# iSENSE_Data_Logger.net
KiCad netlist of a schematic drawn in EAGLE
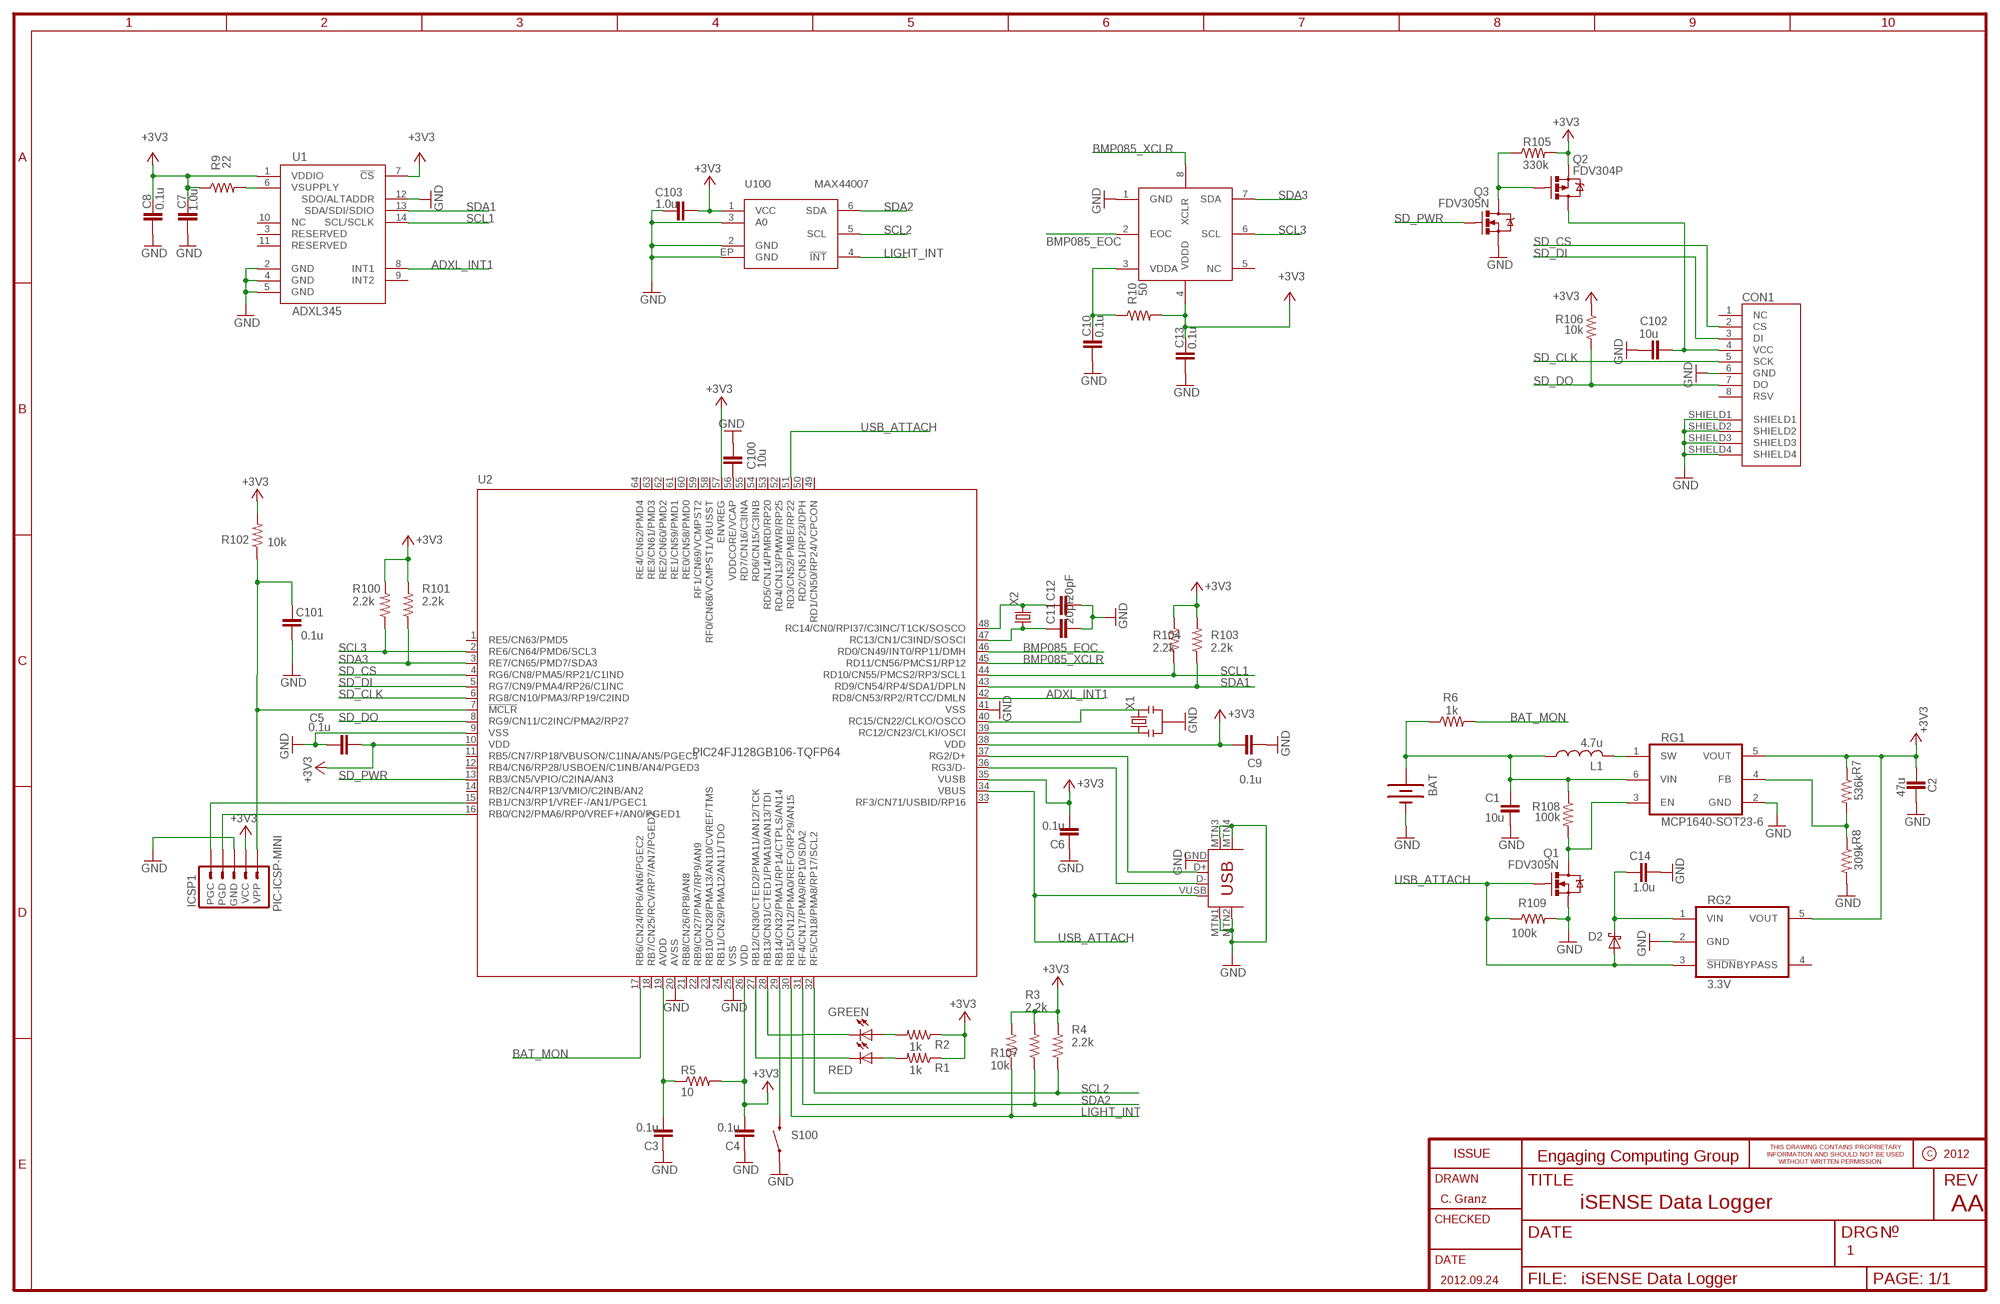
[diagram p0: schematic, sheet 1]

(export (version "E")
  (design (tool "Eeschema 10.0.6"))
  (components
    (comp (ref "BAT")
      (value "BATTERY-AAA-PCB-1-NO-HOLES")
      (footprint "eagle-import:BATTERY_HOLDER_AAA_KEYSTONE_2466_NO_HOLES")
      (libsource (lib "eagle-import") (part "BATTERY-AAA-PCB-1-NO-HOLES"))
    )
    (comp (ref "C1")
      (value "10u")
      (footprint "eagle-import:RCL_0603")
      (libsource (lib "eagle-import") (part "CAPACITOR-0603"))
    )
    (comp (ref "C2")
      (value "47u")
      (footprint "eagle-import:RCL_0603")
      (libsource (lib "eagle-import") (part "CAPACITOR-0603"))
    )
    (comp (ref "C3")
      (value "0.1u")
      (footprint "eagle-import:RCL_0402")
      (libsource (lib "eagle-import") (part "CAPACITOR-0402"))
    )
    (comp (ref "C4")
      (value "0.1u")
      (footprint "eagle-import:RCL_0402")
      (libsource (lib "eagle-import") (part "CAPACITOR-0402"))
    )
    (comp (ref "C5")
      (value "0.1u")
      (footprint "eagle-import:RCL_0402")
      (libsource (lib "eagle-import") (part "CAPACITOR-0402"))
    )
    (comp (ref "C6")
      (value "0.1u")
      (footprint "eagle-import:RCL_0402")
      (libsource (lib "eagle-import") (part "CAPACITOR-0402"))
    )
    (comp (ref "C7")
      (value "1.0u")
      (footprint "eagle-import:RCL_0402")
      (libsource (lib "eagle-import") (part "CAPACITOR-0402"))
    )
    (comp (ref "C8")
      (value "0.1u")
      (footprint "eagle-import:RCL_0402")
      (libsource (lib "eagle-import") (part "CAPACITOR-0402"))
    )
    (comp (ref "C9")
      (value "0.1u")
      (footprint "eagle-import:RCL_0402")
      (libsource (lib "eagle-import") (part "CAPACITOR-0402"))
    )
    (comp (ref "C10")
      (value "0.1u")
      (footprint "eagle-import:RCL_0402")
      (libsource (lib "eagle-import") (part "CAPACITOR-0402"))
    )
    (comp (ref "C11")
      (value "20pF")
      (footprint "eagle-import:RCL_0402")
      (libsource (lib "eagle-import") (part "CAPACITOR-0402"))
    )
    (comp (ref "C12")
      (value "20pF")
      (footprint "eagle-import:RCL_0402")
      (libsource (lib "eagle-import") (part "CAPACITOR-0402"))
    )
    (comp (ref "C13")
      (value "0.1u")
      (footprint "eagle-import:RCL_0402")
      (libsource (lib "eagle-import") (part "CAPACITOR-0402"))
    )
    (comp (ref "C14")
      (value "1.0u")
      (footprint "eagle-import:RCL_0603")
      (libsource (lib "eagle-import") (part "CAPACITOR-0603"))
    )
    (comp (ref "C100")
      (value "10u")
      (footprint "eagle-import:RCL_0603")
      (libsource (lib "eagle-import") (part "CAPACITOR-0603"))
    )
    (comp (ref "C101")
      (value "0.1u")
      (footprint "eagle-import:RCL_0402")
      (libsource (lib "eagle-import") (part "CAPACITOR-0402"))
    )
    (comp (ref "C102")
      (value "10u")
      (footprint "eagle-import:RCL_0402")
      (libsource (lib "eagle-import") (part "CAPACITOR-0402"))
    )
    (comp (ref "C103")
      (value "1.0u")
      (footprint "eagle-import:RCL_0402")
      (libsource (lib "eagle-import") (part "CAPACITOR-0402"))
    )
    (comp (ref "CON1")
      (value "SOCKET_SD_CARD_MICRO-AMP-101-00303-68")
      (footprint "eagle-import:SOCKET_SD_CARD_MICRO")
      (fields (field (name "PN") "101-00303-68"))
      (libsource (lib "eagle-import") (part "SOCKET_SD_CARD_MICRO-AMP-101-00303-68"))
    )
    (comp (ref "D2")
      (value "DIODE_SCHOTTKY-SOD523")
      (footprint "eagle-import:SOD523")
      (libsource (lib "eagle-import") (part "DIODE_SCHOTTKY-SOD523"))
    )
    (comp (ref "GREEN")
      (value "GREEN")
      (footprint "eagle-import:LED_0603")
      (libsource (lib "eagle-import") (part "LED-0603"))
    )
    (comp (ref "ICSP1")
      (value "PIC-ICSP-MINI")
      (footprint "eagle-import:PIC-ICSP-MINI")
      (libsource (lib "eagle-import") (part "PIC-ICSP-MINI"))
    )
    (comp (ref "L1")
      (value "4.7u")
      (footprint "eagle-import:INDUCTOR_3MM_X_3MM")
      (libsource (lib "eagle-import") (part "INDUCTOR-3X3MM"))
    )
    (comp (ref "Q1")
      (value "FDV305N")
      (footprint "eagle-import:SOT23-3")
      (fields (field (name "PN") "FDV305N"))
      (libsource (lib "eagle-import") (part "FDV305N"))
    )
    (comp (ref "Q2")
      (value "FDV304P")
      (footprint "eagle-import:SOT23-3")
      (fields (field (name "PN") "FDV304P"))
      (libsource (lib "eagle-import") (part "FDV302P"))
    )
    (comp (ref "Q3")
      (value "FDV305N")
      (footprint "eagle-import:SOT23-3")
      (fields (field (name "PN") "FDV305N"))
      (libsource (lib "eagle-import") (part "FDV305N"))
    )
    (comp (ref "R1")
      (value "1k")
      (footprint "eagle-import:RCL_0402")
      (libsource (lib "eagle-import") (part "RESISTOR-0402"))
    )
    (comp (ref "R2")
      (value "1k")
      (footprint "eagle-import:RCL_0402")
      (libsource (lib "eagle-import") (part "RESISTOR-0402"))
    )
    (comp (ref "R3")
      (value "2.2k")
      (footprint "eagle-import:RCL_0402")
      (libsource (lib "eagle-import") (part "RESISTOR-0402"))
    )
    (comp (ref "R4")
      (value "2.2k")
      (footprint "eagle-import:RCL_0402")
      (libsource (lib "eagle-import") (part "RESISTOR-0402"))
    )
    (comp (ref "R5")
      (value "10")
      (footprint "eagle-import:RCL_0402")
      (libsource (lib "eagle-import") (part "RESISTOR-0402"))
    )
    (comp (ref "R6")
      (value "1k")
      (footprint "eagle-import:RCL_0402")
      (libsource (lib "eagle-import") (part "RESISTOR-0402"))
    )
    (comp (ref "R7")
      (value "536k")
      (footprint "eagle-import:RCL_0402")
      (libsource (lib "eagle-import") (part "RESISTOR-0402"))
    )
    (comp (ref "R8")
      (value "309k")
      (footprint "eagle-import:RCL_0402")
      (libsource (lib "eagle-import") (part "RESISTOR-0402"))
    )
    (comp (ref "R9")
      (value "22")
      (footprint "eagle-import:RCL_0402")
      (libsource (lib "eagle-import") (part "RESISTOR-0402"))
    )
    (comp (ref "R10")
      (value "50")
      (footprint "eagle-import:RCL_0402")
      (libsource (lib "eagle-import") (part "RESISTOR-0402"))
    )
    (comp (ref "R100")
      (value "2.2k")
      (footprint "eagle-import:RCL_0402")
      (libsource (lib "eagle-import") (part "RESISTOR-0402"))
    )
    (comp (ref "R101")
      (value "2.2k")
      (footprint "eagle-import:RCL_0402")
      (libsource (lib "eagle-import") (part "RESISTOR-0402"))
    )
    (comp (ref "R102")
      (value "10k")
      (footprint "eagle-import:RCL_0402")
      (libsource (lib "eagle-import") (part "RESISTOR-0402"))
    )
    (comp (ref "R103")
      (value "2.2k")
      (footprint "eagle-import:RCL_0402")
      (libsource (lib "eagle-import") (part "RESISTOR-0402"))
    )
    (comp (ref "R104")
      (value "2.2k")
      (footprint "eagle-import:RCL_0402")
      (libsource (lib "eagle-import") (part "RESISTOR-0402"))
    )
    (comp (ref "R105")
      (value "330k")
      (footprint "eagle-import:RCL_0402")
      (libsource (lib "eagle-import") (part "RESISTOR-0402"))
    )
    (comp (ref "R106")
      (value "10k")
      (footprint "eagle-import:RCL_0402")
      (libsource (lib "eagle-import") (part "RESISTOR-0402"))
    )
    (comp (ref "R107")
      (value "10k")
      (footprint "eagle-import:RCL_0402")
      (libsource (lib "eagle-import") (part "RESISTOR-0402"))
    )
    (comp (ref "R108")
      (value "100k")
      (footprint "eagle-import:RCL_0402")
      (libsource (lib "eagle-import") (part "RESISTOR-0402"))
    )
    (comp (ref "R109")
      (value "100k")
      (footprint "eagle-import:RCL_0402")
      (libsource (lib "eagle-import") (part "RESISTOR-0402"))
    )
    (comp (ref "RED")
      (value "RED")
      (footprint "eagle-import:LED_0603")
      (libsource (lib "eagle-import") (part "LED-0603"))
    )
    (comp (ref "RG1")
      (value "MCP1640-SOT23-6")
      (footprint "eagle-import:SOT23-6")
      (libsource (lib "eagle-import") (part "MCP1640-SOT23-6"))
    )
    (comp (ref "RG2")
      (value "3.3V")
      (footprint "eagle-import:SOT23-5")
      (libsource (lib "eagle-import") (part "TC1015"))
    )
    (comp (ref "S100")
      (value "SWITCH_MOMENTARY-SMD-RA")
      (footprint "eagle-import:SWITCH_TACTILE_SMD_RA")
      (libsource (lib "eagle-import") (part "SWITCH_MOMENTARY-SMD-RA"))
    )
    (comp (ref "U1")
      (value "ADXL345")
      (footprint "eagle-import:LGA14")
      (libsource (lib "eagle-import") (part "ADXL345"))
    )
    (comp (ref "U2")
      (value "PIC24FJ128GB106-TQFP64")
      (footprint "eagle-import:TQFP64-10X10")
      (fields (field (name "PN") "PIC24FJ128GB106-I/PT"))
      (libsource (lib "eagle-import") (part "PIC24FJ128GB106-TQFP64"))
    )
    (comp (ref "U3")
      (value "BMP085")
      (footprint "eagle-import:BMP085")
      (fields (field (name "PN") "BMP085"))
      (libsource (lib "eagle-import") (part "BMP085"))
    )
    (comp (ref "U100")
      (value "MAX44007")
      (footprint "eagle-import:UTDFN-OPTO")
      (libsource (lib "eagle-import") (part "MAX44007"))
    )
    (comp (ref "USB100")
      (value "CON_USB_4_PIN-A_MALE")
      (footprint "eagle-import:CON_USB_A_MALE_CNC_TECH_1001-010-01001")
      (fields (field (name "PN") "1001-010-01001"))
      (libsource (lib "eagle-import") (part "CON_USB_4_PIN-A_MALE"))
    )
    (comp (ref "X1")
      (value "CERAMIC_RESONATOR_3_PIN-2MM_X_4.5MM")
      (footprint "eagle-import:CERAMIC_RESONATOR_MURATA_2X4.5")
      (libsource (lib "eagle-import") (part "CERAMIC_RESONATOR_3_PIN-2MM_X_4.5MM"))
    )
    (comp (ref "X2")
      (value "CRYSTAL_2_PIN-4.9MM_X_1.8MM")
      (footprint "eagle-import:CRYSTAL_ABRACON_ABS10")
      (libsource (lib "eagle-import") (part "CRYSTAL_2_PIN-4.9MM_X_1.8MM"))
    )
  )
  (nets
    (net (code "1") (name "+3V3") (class "Default")
      (node (ref "C103") (pin "1") (pinfunction "1_1") (pintype "passive"))
      (node (ref "C13") (pin "2") (pinfunction "2_2") (pintype "passive"))
      (node (ref "C2") (pin "1") (pinfunction "1_1") (pintype "passive"))
      (node (ref "C4") (pin "2") (pinfunction "2_2") (pintype "passive"))
      (node (ref "C5") (pin "1") (pinfunction "1_1") (pintype "passive"))
      (node (ref "C6") (pin "2") (pinfunction "2_2") (pintype "passive"))
      (node (ref "C7") (pin "2") (pinfunction "2_2") (pintype "passive"))
      (node (ref "C8") (pin "2") (pinfunction "2_2") (pintype "passive"))
      (node (ref "C9") (pin "1") (pinfunction "1_1") (pintype "passive"))
      (node (ref "ICSP1") (pin "2") (pinfunction "VCC_2") (pintype "passive"))
      (node (ref "Q2") (pin "2") (pinfunction "S_2") (pintype "passive"))
      (node (ref "R1") (pin "1") (pinfunction "1_1") (pintype "passive"))
      (node (ref "R10") (pin "2") (pinfunction "2_2") (pintype "passive"))
      (node (ref "R100") (pin "2") (pinfunction "2_2") (pintype "passive"))
      (node (ref "R101") (pin "2") (pinfunction "2_2") (pintype "passive"))
      (node (ref "R102") (pin "2") (pinfunction "2_2") (pintype "passive"))
      (node (ref "R103") (pin "2") (pinfunction "2_2") (pintype "passive"))
      (node (ref "R104") (pin "2") (pinfunction "2_2") (pintype "passive"))
      (node (ref "R105") (pin "2") (pinfunction "2_2") (pintype "passive"))
      (node (ref "R106") (pin "1") (pinfunction "1_1") (pintype "passive"))
      (node (ref "R107") (pin "2") (pinfunction "2_2") (pintype "passive"))
      (node (ref "R2") (pin "1") (pinfunction "1_1") (pintype "passive"))
      (node (ref "R3") (pin "2") (pinfunction "2_2") (pintype "passive"))
      (node (ref "R4") (pin "2") (pinfunction "2_2") (pintype "passive"))
      (node (ref "R5") (pin "2") (pinfunction "2_2") (pintype "passive"))
      (node (ref "R7") (pin "1") (pinfunction "1_1") (pintype "passive"))
      (node (ref "R9") (pin "1") (pinfunction "1_1") (pintype "passive"))
      (node (ref "RG1") (pin "5") (pinfunction "VOUT_5") (pintype "power_in"))
      (node (ref "RG2") (pin "5") (pinfunction "VOUT_5") (pintype "power_in"))
      (node (ref "U1") (pin "1") (pinfunction "VDDIO_1") (pintype "power_in"))
      (node (ref "U1") (pin "7") (pinfunction "~{CS}_7") (pintype "input"))
      (node (ref "U100") (pin "1") (pinfunction "VCC_1") (pintype "bidirectional"))
      (node (ref "U2") (pin "10") (pinfunction "VDD_10") (pintype "power_in"))
      (node (ref "U2") (pin "26") (pinfunction "VDD_26") (pintype "power_in"))
      (node (ref "U2") (pin "35") (pinfunction "VUSB_35") (pintype "bidirectional"))
      (node (ref "U2") (pin "38") (pinfunction "VDD_38") (pintype "power_in"))
      (node (ref "U2") (pin "57") (pinfunction "ENVREG_57") (pintype "bidirectional"))
      (node (ref "U3") (pin "4") (pinfunction "VDDD_4") (pintype "power_in"))
    )
    (net (code "2") (name "/ADXL_INT1") (class "Default")
      (node (ref "U1") (pin "8") (pinfunction "INT1_8") (pintype "output"))
      (node (ref "U2") (pin "42") (pinfunction "RD8/CN53/RP2/RTCC/DMLN_42") (pintype "bidirectional"))
    )
    (net (code "3") (name "/BAT_MON") (class "Default")
      (node (ref "R6") (pin "2") (pinfunction "2_2") (pintype "passive"))
      (node (ref "U2") (pin "17") (pinfunction "RB6/CN24/RP6/AN6/PGEC2_17") (pintype "bidirectional"))
    )
    (net (code "4") (name "/BMP085_EOC") (class "Default")
      (node (ref "U2") (pin "46") (pinfunction "RD0/CN49/INT0/RP11/DMH_46") (pintype "bidirectional"))
      (node (ref "U3") (pin "2") (pinfunction "EOC_2") (pintype "bidirectional"))
    )
    (net (code "5") (name "/BMP085_XCLR") (class "Default")
      (node (ref "U2") (pin "45") (pinfunction "RD11/CN56/PMCS1/RP12_45") (pintype "bidirectional"))
      (node (ref "U3") (pin "8") (pinfunction "XCLR_8") (pintype "input"))
    )
    (net (code "6") (name "/LIGHT_INT") (class "Default")
      (node (ref "R107") (pin "1") (pinfunction "1_1") (pintype "passive"))
      (node (ref "U100") (pin "4") (pinfunction "~{INT}_4") (pintype "output"))
      (node (ref "U2") (pin "30") (pinfunction "RB15/CN12/PMA0/REFO/RP29/AN15_30") (pintype "bidirectional"))
    )
    (net (code "7") (name "/SCL1") (class "Default")
      (node (ref "R104") (pin "1") (pinfunction "1_1") (pintype "passive"))
      (node (ref "U1") (pin "14") (pinfunction "SCL/SCLK_14") (pintype "input"))
      (node (ref "U2") (pin "44") (pinfunction "RD10/CN55/PMCS2/RP3/SCL1_44") (pintype "bidirectional"))
    )
    (net (code "8") (name "/SCL2") (class "Default")
      (node (ref "R4") (pin "1") (pinfunction "1_1") (pintype "passive"))
      (node (ref "U100") (pin "5") (pinfunction "SCL_5") (pintype "input"))
      (node (ref "U2") (pin "32") (pinfunction "RF5/CN18/PMA8/RP17/SCL2_32") (pintype "bidirectional"))
    )
    (net (code "9") (name "/SCL3") (class "Default")
      (node (ref "R100") (pin "1") (pinfunction "1_1") (pintype "passive"))
      (node (ref "U2") (pin "2") (pinfunction "RE6/CN64/PMD6/SCL3_2") (pintype "bidirectional"))
      (node (ref "U3") (pin "6") (pinfunction "SCL_6") (pintype "input"))
    )
    (net (code "10") (name "/SDA1") (class "Default")
      (node (ref "R103") (pin "1") (pinfunction "1_1") (pintype "passive"))
      (node (ref "U1") (pin "13") (pinfunction "SDA/SDI/SDIO_13") (pintype "bidirectional"))
      (node (ref "U2") (pin "43") (pinfunction "RD9/CN54/RP4/SDA1/DPLN_43") (pintype "bidirectional"))
    )
    (net (code "11") (name "/SDA2") (class "Default")
      (node (ref "R3") (pin "1") (pinfunction "1_1") (pintype "passive"))
      (node (ref "U100") (pin "6") (pinfunction "SDA_6") (pintype "bidirectional"))
      (node (ref "U2") (pin "31") (pinfunction "RF4/CN17/PMA9/RP10/SDA2_31") (pintype "bidirectional"))
    )
    (net (code "12") (name "/SDA3") (class "Default")
      (node (ref "R101") (pin "1") (pinfunction "1_1") (pintype "passive"))
      (node (ref "U2") (pin "3") (pinfunction "RE7/CN65/PMD7/SDA3_3") (pintype "bidirectional"))
      (node (ref "U3") (pin "7") (pinfunction "SDA_7") (pintype "bidirectional"))
    )
    (net (code "13") (name "/SD_CLK") (class "Default")
      (node (ref "CON1") (pin "5") (pinfunction "SCK_5") (pintype "input"))
      (node (ref "U2") (pin "6") (pinfunction "RG8/CN10/PMA3/RP19/C2IND_6") (pintype "bidirectional"))
    )
    (net (code "14") (name "/SD_CS") (class "Default")
      (node (ref "CON1") (pin "2") (pinfunction "CS_2") (pintype "input"))
      (node (ref "U2") (pin "4") (pinfunction "RG6/CN8/PMA5/RP21/C1IND_4") (pintype "bidirectional"))
    )
    (net (code "15") (name "/SD_DI") (class "Default")
      (node (ref "CON1") (pin "3") (pinfunction "DI_3") (pintype "input"))
      (node (ref "U2") (pin "5") (pinfunction "RG7/CN9/PMA4/RP26/C1INC_5") (pintype "bidirectional"))
    )
    (net (code "16") (name "/SD_DO") (class "Default")
      (node (ref "CON1") (pin "7") (pinfunction "DO_7") (pintype "output"))
      (node (ref "R106") (pin "2") (pinfunction "2_2") (pintype "passive"))
      (node (ref "U2") (pin "8") (pinfunction "RG9/CN11/C2INC/PMA2/RP27_8") (pintype "bidirectional"))
    )
    (net (code "17") (name "/SD_PWR") (class "Default")
      (node (ref "Q3") (pin "1") (pinfunction "G_1") (pintype "passive"))
      (node (ref "U2") (pin "13") (pinfunction "RB3/CN5/VPIO/C2INA/AN3_13") (pintype "bidirectional"))
    )
    (net (code "18") (name "/USB_ATTACH") (class "Default")
      (node (ref "D2") (pin "A") (pinfunction "A_A") (pintype "passive"))
      (node (ref "Q1") (pin "1") (pinfunction "G_1") (pintype "passive"))
      (node (ref "R109") (pin "1") (pinfunction "1_1") (pintype "passive"))
      (node (ref "RG2") (pin "3") (pinfunction "~{SHDN}_3") (pintype "input"))
      (node (ref "U2") (pin "34") (pinfunction "VBUS_34") (pintype "bidirectional"))
      (node (ref "U2") (pin "51") (pinfunction "RD3/CN52/PMBE/RP22_51") (pintype "bidirectional"))
      (node (ref "USB100") (pin "VUSB") (pinfunction "VBUS_VUSB") (pintype "power_in"))
    )
    (net (code "19") (name "GND") (class "Default")
      (node (ref "BAT") (pin "-") (pinfunction "-_-") (pintype "power_in"))
      (node (ref "C1") (pin "2") (pinfunction "2_2") (pintype "passive"))
      (node (ref "C10") (pin "1") (pinfunction "1_1") (pintype "passive"))
      (node (ref "C100") (pin "2") (pinfunction "2_2") (pintype "passive"))
      (node (ref "C101") (pin "2") (pinfunction "2_2") (pintype "passive"))
      (node (ref "C102") (pin "1") (pinfunction "1_1") (pintype "passive"))
      (node (ref "C103") (pin "2") (pinfunction "2_2") (pintype "passive"))
      (node (ref "C11") (pin "2") (pinfunction "2_2") (pintype "passive"))
      (node (ref "C12") (pin "2") (pinfunction "2_2") (pintype "passive"))
      (node (ref "C13") (pin "1") (pinfunction "1_1") (pintype "passive"))
      (node (ref "C14") (pin "2") (pinfunction "2_2") (pintype "passive"))
      (node (ref "C2") (pin "2") (pinfunction "2_2") (pintype "passive"))
      (node (ref "C3") (pin "1") (pinfunction "1_1") (pintype "passive"))
      (node (ref "C4") (pin "1") (pinfunction "1_1") (pintype "passive"))
      (node (ref "C5") (pin "2") (pinfunction "2_2") (pintype "passive"))
      (node (ref "C6") (pin "1") (pinfunction "1_1") (pintype "passive"))
      (node (ref "C7") (pin "1") (pinfunction "1_1") (pintype "passive"))
      (node (ref "C8") (pin "1") (pinfunction "1_1") (pintype "passive"))
      (node (ref "C9") (pin "2") (pinfunction "2_2") (pintype "passive"))
      (node (ref "CON1") (pin "6") (pinfunction "GND_6") (pintype "power_in"))
      (node (ref "CON1") (pin "SHIELD1") (pinfunction "SHIELD1_SHIELD1") (pintype "passive"))
      (node (ref "CON1") (pin "SHIELD2") (pinfunction "SHIELD2_SHIELD2") (pintype "passive"))
      (node (ref "CON1") (pin "SHIELD3") (pinfunction "SHIELD3_SHIELD3") (pintype "passive"))
      (node (ref "CON1") (pin "SHIELD4") (pinfunction "SHIELD4_SHIELD4") (pintype "passive"))
      (node (ref "ICSP1") (pin "3") (pinfunction "GND_3") (pintype "passive"))
      (node (ref "Q1") (pin "2") (pinfunction "S_2") (pintype "passive"))
      (node (ref "Q3") (pin "2") (pinfunction "S_2") (pintype "passive"))
      (node (ref "R109") (pin "2") (pinfunction "2_2") (pintype "passive"))
      (node (ref "R8") (pin "2") (pinfunction "2_2") (pintype "passive"))
      (node (ref "RG1") (pin "2") (pinfunction "GND_2") (pintype "power_in"))
      (node (ref "RG2") (pin "2") (pinfunction "GND_2") (pintype "power_in"))
      (node (ref "S100") (pin "1") (pinfunction "1_1") (pintype "passive"))
      (node (ref "U1") (pin "12") (pinfunction "SDO/ALTADDR_12") (pintype "bidirectional"))
      (node (ref "U1") (pin "2") (pinfunction "GND_2") (pintype "power_in"))
      (node (ref "U1") (pin "4") (pinfunction "GND_4") (pintype "power_in"))
      (node (ref "U1") (pin "5") (pinfunction "GND_5") (pintype "power_in"))
      (node (ref "U100") (pin "2") (pinfunction "GND_2") (pintype "power_in"))
      (node (ref "U100") (pin "3") (pinfunction "A0_3") (pintype "bidirectional"))
      (node (ref "U100") (pin "EP") (pinfunction "GND_EP") (pintype "power_in"))
      (node (ref "U2") (pin "20") (pinfunction "AVSS_20") (pintype "power_in"))
      (node (ref "U2") (pin "25") (pinfunction "VSS_25") (pintype "power_in"))
      (node (ref "U2") (pin "41") (pinfunction "VSS_41") (pintype "power_in"))
      (node (ref "U2") (pin "9") (pinfunction "VSS_9") (pintype "power_in"))
      (node (ref "U3") (pin "1") (pinfunction "GND_1") (pintype "power_in"))
      (node (ref "USB100") (pin "GND") (pinfunction "GND_GND") (pintype "power_in"))
      (node (ref "USB100") (pin "MTN1") (pinfunction "MTN1_MTN1") (pintype "passive"))
      (node (ref "USB100") (pin "MTN2") (pinfunction "MTN2_MTN2") (pintype "passive"))
      (node (ref "USB100") (pin "MTN3") (pinfunction "MTN3_MTN3") (pintype "passive"))
      (node (ref "USB100") (pin "MTN4") (pinfunction "MTN4_MTN4") (pintype "passive"))
      (node (ref "X1") (pin "2") (pinfunction "2_2") (pintype "passive"))
    )
    (net (code "20") (name "Net-(CON1-VCC)") (class "Default")
      (node (ref "C102") (pin "2") (pinfunction "2_2") (pintype "passive"))
      (node (ref "CON1") (pin "4") (pinfunction "VCC_4") (pintype "power_in"))
      (node (ref "Q2") (pin "3") (pinfunction "D_3") (pintype "passive"))
    )
    (net (code "21") (name "Net-(GREEN-PadA)") (class "Default")
      (node (ref "GREEN") (pin "A") (pinfunction "A_A") (pintype "passive"))
      (node (ref "R2") (pin "2") (pinfunction "2_2") (pintype "passive"))
    )
    (net (code "22") (name "Net-(ICSP1-PGC)") (class "Default")
      (node (ref "ICSP1") (pin "5") (pinfunction "PGC_5") (pintype "passive"))
      (node (ref "U2") (pin "15") (pinfunction "RB1/CN3/RP1/VREF-/AN1/PGEC1_15") (pintype "bidirectional"))
    )
    (net (code "23") (name "Net-(ICSP1-PGD)") (class "Default")
      (node (ref "ICSP1") (pin "4") (pinfunction "PGD_4") (pintype "passive"))
      (node (ref "U2") (pin "16") (pinfunction "RB0/CN2/PMA6/RP0/VREF+/AN0/PGED1_16") (pintype "bidirectional"))
    )
    (net (code "24") (name "Net-(ICSP1-VPP)") (class "Default")
      (node (ref "C101") (pin "1") (pinfunction "1_1") (pintype "passive"))
      (node (ref "ICSP1") (pin "1") (pinfunction "VPP_1") (pintype "passive"))
      (node (ref "R102") (pin "1") (pinfunction "1_1") (pintype "passive"))
      (node (ref "U2") (pin "7") (pinfunction "~{MCLR}_7") (pintype "bidirectional"))
    )
    (net (code "25") (name "Net-(Q1-D)") (class "Default")
      (node (ref "Q1") (pin "3") (pinfunction "D_3") (pintype "passive"))
      (node (ref "R108") (pin "2") (pinfunction "2_2") (pintype "passive"))
      (node (ref "RG1") (pin "3") (pinfunction "EN_3") (pintype "input"))
    )
    (net (code "26") (name "Net-(Q2-G)") (class "Default")
      (node (ref "Q2") (pin "1") (pinfunction "G_1") (pintype "passive"))
      (node (ref "Q3") (pin "3") (pinfunction "D_3") (pintype "passive"))
      (node (ref "R105") (pin "1") (pinfunction "1_1") (pintype "passive"))
    )
    (net (code "27") (name "Net-(R1-Pad2)") (class "Default")
      (node (ref "R1") (pin "2") (pinfunction "2_2") (pintype "passive"))
      (node (ref "RED") (pin "A") (pinfunction "A_A") (pintype "passive"))
    )
    (net (code "28") (name "Net-(RG1-FB)") (class "Default")
      (node (ref "R7") (pin "2") (pinfunction "2_2") (pintype "passive"))
      (node (ref "R8") (pin "1") (pinfunction "1_1") (pintype "passive"))
      (node (ref "RG1") (pin "4") (pinfunction "FB_4") (pintype "input"))
    )
    (net (code "29") (name "Net-(RG1-SW)") (class "Default")
      (node (ref "L1") (pin "2") (pinfunction "2_2") (pintype "passive"))
      (node (ref "RG1") (pin "1") (pinfunction "SW_1") (pintype "passive"))
    )
    (net (code "30") (name "Net-(RG1-VIN)") (class "Default")
      (node (ref "BAT") (pin "+") (pinfunction "+_+") (pintype "power_in"))
      (node (ref "C1") (pin "1") (pinfunction "1_1") (pintype "passive"))
      (node (ref "L1") (pin "1") (pinfunction "1_1") (pintype "passive"))
      (node (ref "R108") (pin "1") (pinfunction "1_1") (pintype "passive"))
      (node (ref "R6") (pin "1") (pinfunction "1_1") (pintype "passive"))
      (node (ref "RG1") (pin "6") (pinfunction "VIN_6") (pintype "power_in"))
    )
    (net (code "31") (name "Net-(RG2-VIN)") (class "Default")
      (node (ref "C14") (pin "1") (pinfunction "1_1") (pintype "passive"))
      (node (ref "D2") (pin "C") (pinfunction "C_C") (pintype "passive"))
      (node (ref "RG2") (pin "1") (pinfunction "VIN_1") (pintype "power_in"))
    )
    (net (code "32") (name "Net-(U1-VSUPPLY)") (class "Default")
      (node (ref "R9") (pin "2") (pinfunction "2_2") (pintype "passive"))
      (node (ref "U1") (pin "6") (pinfunction "VSUPPLY_6") (pintype "power_in"))
    )
    (net (code "33") (name "Net-(U2-AVDD)") (class "Default")
      (node (ref "C3") (pin "2") (pinfunction "2_2") (pintype "passive"))
      (node (ref "R5") (pin "1") (pinfunction "1_1") (pintype "passive"))
      (node (ref "U2") (pin "19") (pinfunction "AVDD_19") (pintype "power_in"))
    )
    (net (code "34") (name "Net-(U2-RB12{slash}CN30{slash}CTED2{slash}PMA11{slash}AN12{slash}TCK)") (class "Default")
      (node (ref "RED") (pin "C") (pinfunction "C_C") (pintype "passive"))
      (node (ref "U2") (pin "27") (pinfunction "RB12/CN30/CTED2/PMA11/AN12/TCK_27") (pintype "bidirectional"))
    )
    (net (code "35") (name "Net-(U2-RB13{slash}CN31{slash}CTED1{slash}PMA10{slash}AN13{slash}TDI)") (class "Default")
      (node (ref "GREEN") (pin "C") (pinfunction "C_C") (pintype "passive"))
      (node (ref "U2") (pin "28") (pinfunction "RB13/CN31/CTED1/PMA10/AN13/TDI_28") (pintype "bidirectional"))
    )
    (net (code "36") (name "Net-(U2-RB14{slash}CN32{slash}PMA1{slash}RP14{slash}CTPLS{slash}AN14)") (class "Default")
      (node (ref "S100") (pin "2") (pinfunction "2_2") (pintype "passive"))
      (node (ref "U2") (pin "29") (pinfunction "RB14/CN32/PMA1/RP14/CTPLS/AN14_29") (pintype "bidirectional"))
    )
    (net (code "37") (name "Net-(U2-RC12{slash}CN23{slash}CLKI{slash}OSCI)") (class "Default")
      (node (ref "U2") (pin "39") (pinfunction "RC12/CN23/CLKI/OSCI_39") (pintype "bidirectional"))
      (node (ref "X1") (pin "1") (pinfunction "1_1") (pintype "passive"))
    )
    (net (code "38") (name "Net-(U2-RC13{slash}CN1{slash}C3IND{slash}SOSCI)") (class "Default")
      (node (ref "C11") (pin "1") (pinfunction "1_1") (pintype "passive"))
      (node (ref "U2") (pin "47") (pinfunction "RC13/CN1/C3IND/SOSCI_47") (pintype "bidirectional"))
      (node (ref "X2") (pin "1") (pinfunction "1_1") (pintype "passive"))
    )
    (net (code "39") (name "Net-(U2-RC14{slash}CN0{slash}RPI37{slash}C3INC{slash}T1CK{slash}SOSCO)") (class "Default")
      (node (ref "C12") (pin "1") (pinfunction "1_1") (pintype "passive"))
      (node (ref "U2") (pin "48") (pinfunction "RC14/CN0/RPI37/C3INC/T1CK/SOSCO_48") (pintype "bidirectional"))
      (node (ref "X2") (pin "2") (pinfunction "2_2") (pintype "passive"))
    )
    (net (code "40") (name "Net-(U2-RC15{slash}CN22{slash}CLKO{slash}OSCO)") (class "Default")
      (node (ref "U2") (pin "40") (pinfunction "RC15/CN22/CLKO/OSCO_40") (pintype "bidirectional"))
      (node (ref "X1") (pin "3") (pinfunction "3_3") (pintype "passive"))
    )
    (net (code "41") (name "Net-(U2-RG2{slash}D+)") (class "Default")
      (node (ref "U2") (pin "37") (pinfunction "RG2/D+_37") (pintype "bidirectional"))
      (node (ref "USB100") (pin "D+") (pinfunction "D+_D+") (pintype "bidirectional"))
    )
    (net (code "42") (name "Net-(U2-RG3{slash}D-)") (class "Default")
      (node (ref "U2") (pin "36") (pinfunction "RG3/D-_36") (pintype "bidirectional"))
      (node (ref "USB100") (pin "D-") (pinfunction "D-_D-") (pintype "bidirectional"))
    )
    (net (code "43") (name "Net-(U2-VDDCORE{slash}VCAP)") (class "Default")
      (node (ref "C100") (pin "1") (pinfunction "1_1") (pintype "passive"))
      (node (ref "U2") (pin "56") (pinfunction "VDDCORE/VCAP_56") (pintype "bidirectional"))
    )
    (net (code "44") (name "Net-(U3-VDDA)") (class "Default")
      (node (ref "C10") (pin "2") (pinfunction "2_2") (pintype "passive"))
      (node (ref "R10") (pin "1") (pinfunction "1_1") (pintype "passive"))
      (node (ref "U3") (pin "3") (pinfunction "VDDA_3") (pintype "power_in"))
    )
    (net (code "45") (name "unconnected-(CON1-NC-Pad1)") (class "Default")
      (node (ref "CON1") (pin "1") (pinfunction "NC_1") (pintype "no_connect"))
    )
    (net (code "46") (name "unconnected-(CON1-RSV-Pad8)") (class "Default")
      (node (ref "CON1") (pin "8") (pinfunction "RSV_8") (pintype "no_connect"))
    )
    (net (code "47") (name "unconnected-(RG2-BYPASS-Pad4)") (class "Default")
      (node (ref "RG2") (pin "4") (pinfunction "BYPASS_4") (pintype "passive"))
    )
    (net (code "48") (name "unconnected-(U1-INT2-Pad9)") (class "Default")
      (node (ref "U1") (pin "9") (pinfunction "INT2_9") (pintype "output"))
    )
    (net (code "49") (name "unconnected-(U1-NC-Pad10)") (class "Default")
      (node (ref "U1") (pin "10") (pinfunction "NC_10") (pintype "no_connect"))
    )
    (net (code "50") (name "unconnected-(U1-RESERVED-Pad3)") (class "Default")
      (node (ref "U1") (pin "3") (pinfunction "RESERVED_3") (pintype "passive"))
    )
    (net (code "51") (name "unconnected-(U1-RESERVED-Pad11)") (class "Default")
      (node (ref "U1") (pin "11") (pinfunction "RESERVED_11") (pintype "passive"))
    )
    (net (code "52") (name "unconnected-(U2-RB2{slash}CN4{slash}RP13{slash}VMIO{slash}C2INB{slash}AN2-Pad14)") (class "Default")
      (node (ref "U2") (pin "14") (pinfunction "RB2/CN4/RP13/VMIO/C2INB/AN2_14") (pintype "bidirectional"))
    )
    (net (code "53") (name "unconnected-(U2-RB4{slash}CN6{slash}RP28{slash}USBOEN{slash}C1INB{slash}AN4{slash}PGED3-Pad12)") (class "Default")
      (node (ref "U2") (pin "12") (pinfunction "RB4/CN6/RP28/USBOEN/C1INB/AN4/PGED3_12") (pintype "bidirectional"))
    )
    (net (code "54") (name "unconnected-(U2-RB5{slash}CN7{slash}RP18{slash}VBUSON{slash}C1INA{slash}AN5{slash}PGEC3-Pad11)") (class "Default")
      (node (ref "U2") (pin "11") (pinfunction "RB5/CN7/RP18/VBUSON/C1INA/AN5/PGEC3_11") (pintype "bidirectional"))
    )
    (net (code "55") (name "unconnected-(U2-RB7{slash}CN25{slash}RCV{slash}RP7{slash}AN7{slash}PGED2-Pad18)") (class "Default")
      (node (ref "U2") (pin "18") (pinfunction "RB7/CN25/RCV/RP7/AN7/PGED2_18") (pintype "bidirectional"))
    )
    (net (code "56") (name "unconnected-(U2-RB8{slash}CN26{slash}RP8{slash}AN8-Pad21)") (class "Default")
      (node (ref "U2") (pin "21") (pinfunction "RB8/CN26/RP8/AN8_21") (pintype "bidirectional"))
    )
    (net (code "57") (name "unconnected-(U2-RB9{slash}CN27{slash}PMA7{slash}RP9{slash}AN9-Pad22)") (class "Default")
      (node (ref "U2") (pin "22") (pinfunction "RB9/CN27/PMA7/RP9/AN9_22") (pintype "bidirectional"))
    )
    (net (code "58") (name "unconnected-(U2-RB10{slash}CN28{slash}PMA13{slash}AN10{slash}CVREF{slash}TMS-Pad23)") (class "Default")
      (node (ref "U2") (pin "23") (pinfunction "RB10/CN28/PMA13/AN10/CVREF/TMS_23") (pintype "bidirectional"))
    )
    (net (code "59") (name "unconnected-(U2-RB11{slash}CN29{slash}PMA12{slash}AN11{slash}TDO-Pad24)") (class "Default")
      (node (ref "U2") (pin "24") (pinfunction "RB11/CN29/PMA12/AN11/TDO_24") (pintype "bidirectional"))
    )
    (net (code "60") (name "unconnected-(U2-RD1{slash}CN50{slash}RP24{slash}VCPCON-Pad49)") (class "Default")
      (node (ref "U2") (pin "49") (pinfunction "RD1/CN50/RP24/VCPCON_49") (pintype "bidirectional"))
    )
    (net (code "61") (name "unconnected-(U2-RD2{slash}CN51{slash}RP23{slash}DPH-Pad50)") (class "Default")
      (node (ref "U2") (pin "50") (pinfunction "RD2/CN51/RP23/DPH_50") (pintype "bidirectional"))
    )
    (net (code "62") (name "unconnected-(U2-RD4{slash}CN13{slash}PMWR{slash}RP25-Pad52)") (class "Default")
      (node (ref "U2") (pin "52") (pinfunction "RD4/CN13/PMWR/RP25_52") (pintype "bidirectional"))
    )
    (net (code "63") (name "unconnected-(U2-RD5{slash}CN14{slash}PMRD{slash}RP20-Pad53)") (class "Default")
      (node (ref "U2") (pin "53") (pinfunction "RD5/CN14/PMRD/RP20_53") (pintype "bidirectional"))
    )
    (net (code "64") (name "unconnected-(U2-RD6{slash}CN15{slash}C3INB-Pad54)") (class "Default")
      (node (ref "U2") (pin "54") (pinfunction "RD6/CN15/C3INB_54") (pintype "bidirectional"))
    )
    (net (code "65") (name "unconnected-(U2-RD7{slash}CN16{slash}C3INA-Pad55)") (class "Default")
      (node (ref "U2") (pin "55") (pinfunction "RD7/CN16/C3INA_55") (pintype "bidirectional"))
    )
    (net (code "66") (name "unconnected-(U2-RE0{slash}CN58{slash}PMD0-Pad60)") (class "Default")
      (node (ref "U2") (pin "60") (pinfunction "RE0/CN58/PMD0_60") (pintype "bidirectional"))
    )
    (net (code "67") (name "unconnected-(U2-RE1{slash}CN59{slash}PMD1-Pad61)") (class "Default")
      (node (ref "U2") (pin "61") (pinfunction "RE1/CN59/PMD1_61") (pintype "bidirectional"))
    )
    (net (code "68") (name "unconnected-(U2-RE2{slash}CN60{slash}PMD2-Pad62)") (class "Default")
      (node (ref "U2") (pin "62") (pinfunction "RE2/CN60/PMD2_62") (pintype "bidirectional"))
    )
    (net (code "69") (name "unconnected-(U2-RE3{slash}CN61{slash}PMD3-Pad63)") (class "Default")
      (node (ref "U2") (pin "63") (pinfunction "RE3/CN61/PMD3_63") (pintype "bidirectional"))
    )
    (net (code "70") (name "unconnected-(U2-RE4{slash}CN62{slash}PMD4-Pad64)") (class "Default")
      (node (ref "U2") (pin "64") (pinfunction "RE4/CN62/PMD4_64") (pintype "bidirectional"))
    )
    (net (code "71") (name "unconnected-(U2-RE5{slash}CN63{slash}PMD5-Pad1)") (class "Default")
      (node (ref "U2") (pin "1") (pinfunction "RE5/CN63/PMD5_1") (pintype "bidirectional"))
    )
    (net (code "72") (name "unconnected-(U2-RF0{slash}CN68{slash}VCMPST1{slash}VBUSST-Pad58)") (class "Default")
      (node (ref "U2") (pin "58") (pinfunction "RF0/CN68/VCMPST1/VBUSST_58") (pintype "bidirectional"))
    )
    (net (code "73") (name "unconnected-(U2-RF1{slash}CN69{slash}VCMPST2-Pad59)") (class "Default")
      (node (ref "U2") (pin "59") (pinfunction "RF1/CN69/VCMPST2_59") (pintype "bidirectional"))
    )
    (net (code "74") (name "unconnected-(U2-RF3{slash}CN71{slash}USBID{slash}RP16-Pad33)") (class "Default")
      (node (ref "U2") (pin "33") (pinfunction "RF3/CN71/USBID/RP16_33") (pintype "bidirectional"))
    )
    (net (code "75") (name "unconnected-(U3-NC-Pad5)") (class "Default")
      (node (ref "U3") (pin "5") (pinfunction "NC_5") (pintype "no_connect"))
    )
  )
)
